# 10_LMS3_RF.net
KiCad netlist of a schematic drawn in Altium Designer
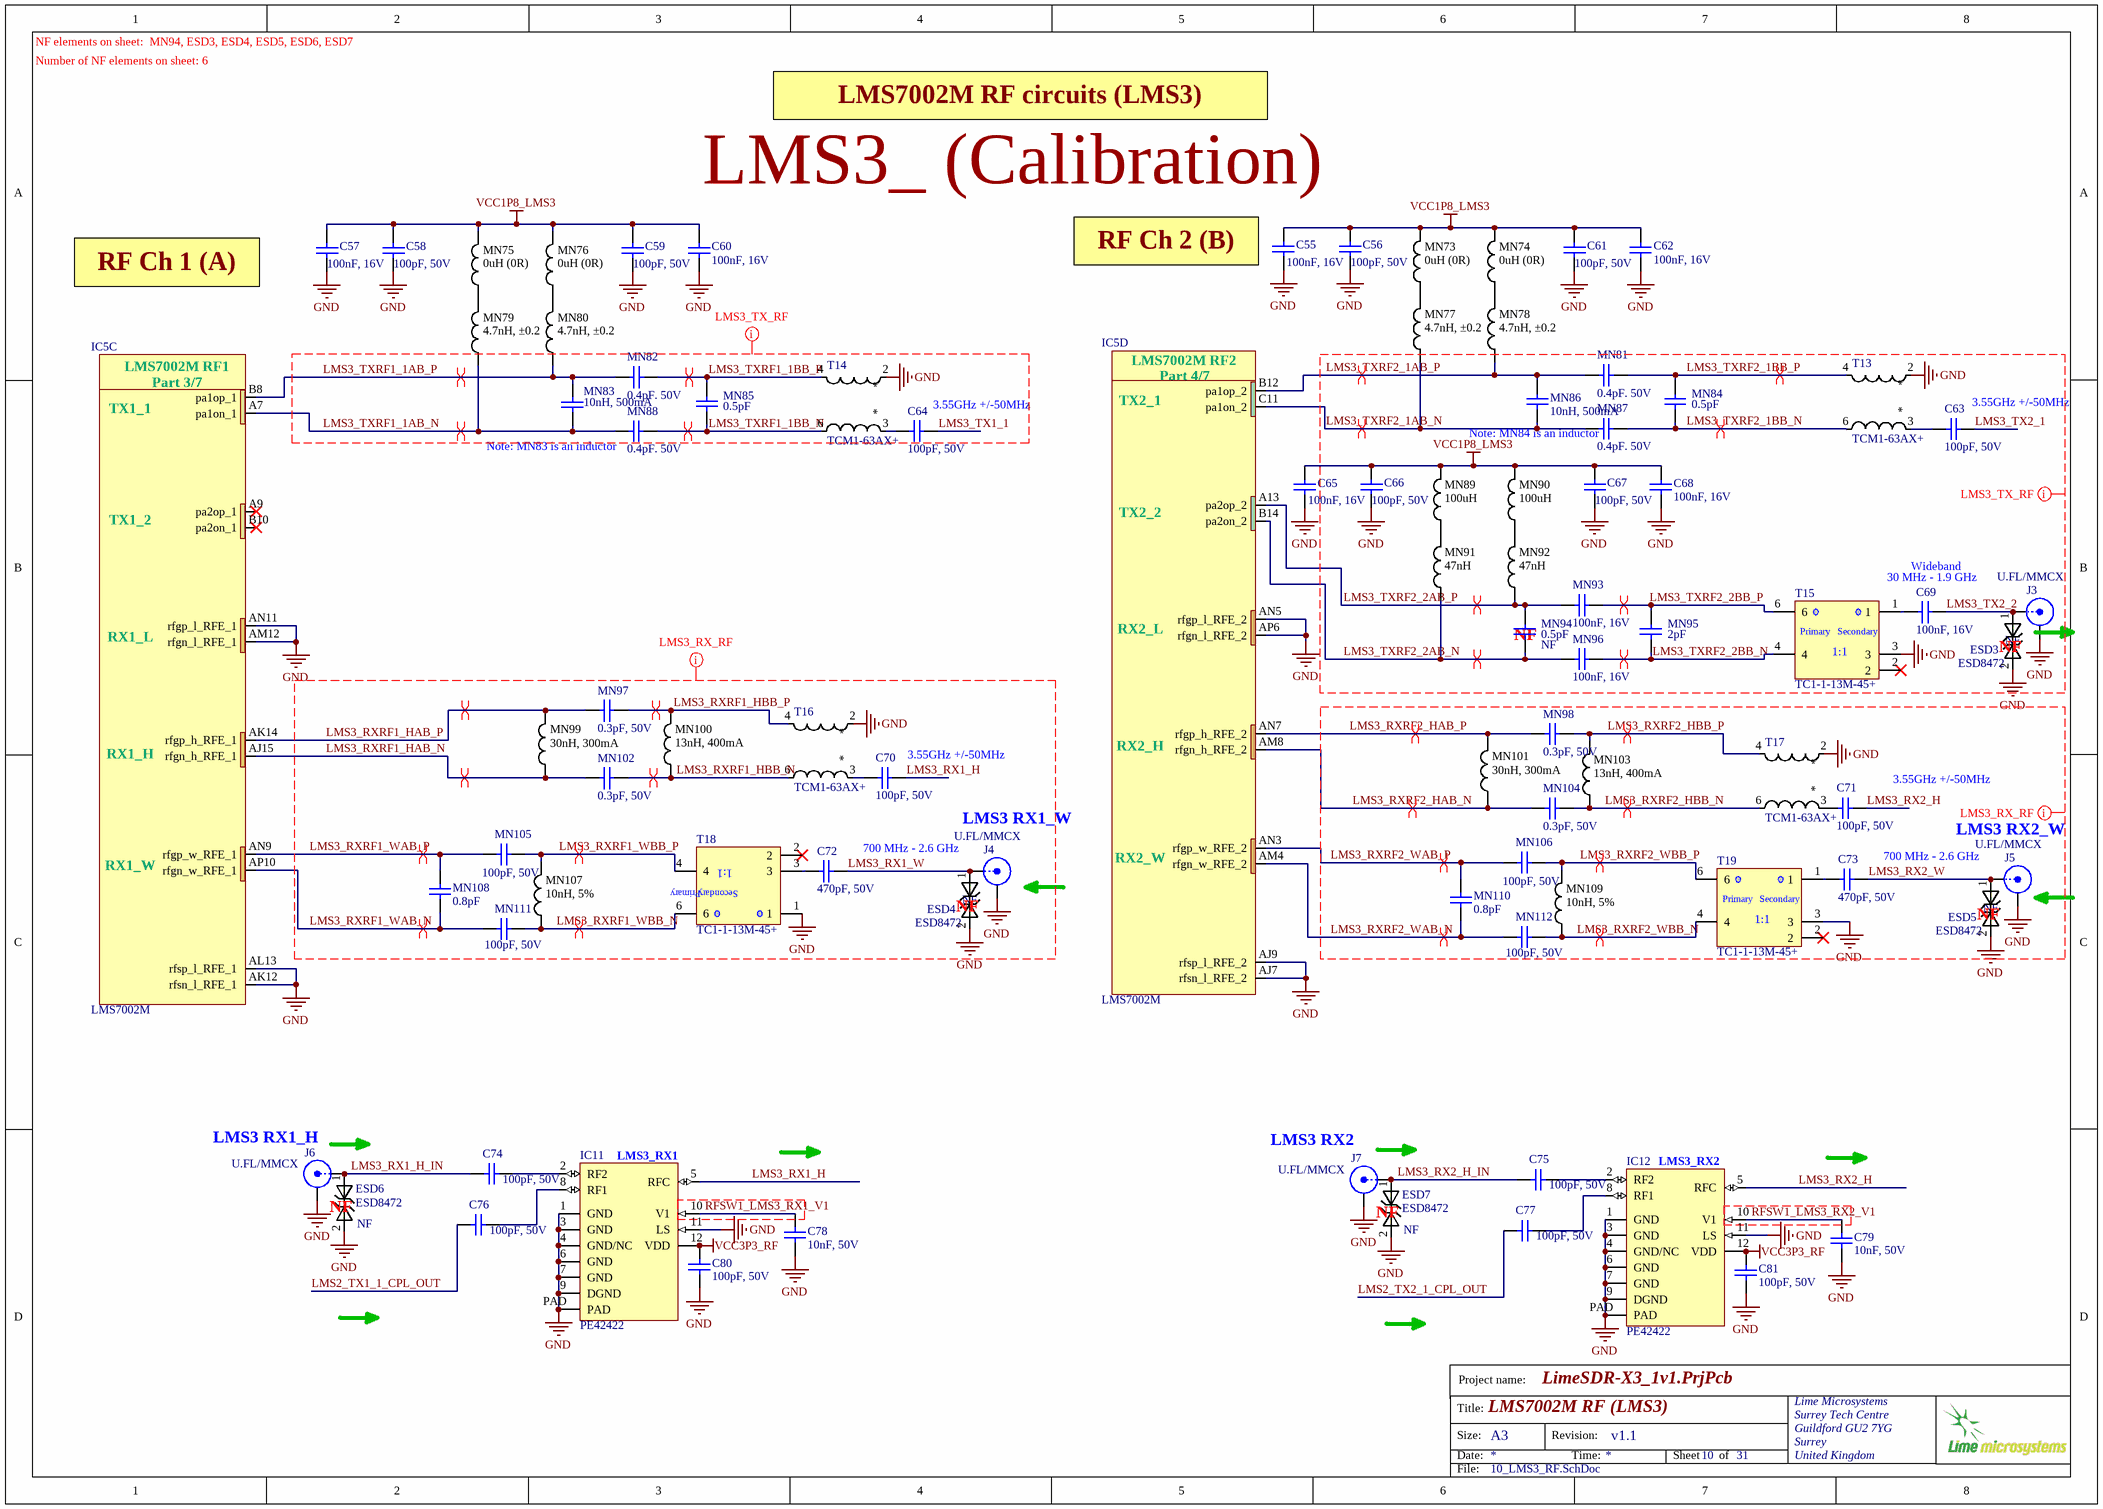
[diagram p0: 10_LMS3_RF.SchDoc]

(export (version "E")
  (design (tool "Eeschema 10.0.6"))
  (components
    (comp (ref "C55")
      (value "100nF, 16V")
      (footprint "CAP0402")
      (fields (field (name "MANUFACTURER") "Murata Electronics") (field (name "TOLERANCE") "10 %"))
      (libsource (lib "") (part "Cap_0402_2"))
    )
    (comp (ref "C56")
      (value "100pF, 50V")
      (footprint "CAP0402")
      (fields (field (name "MANUFACTURER") "Yageo") (field (name "TOLERANCE") "±5%"))
      (libsource (lib "") (part "Cap_0402_1"))
    )
    (comp (ref "C57")
      (value "100nF, 16V")
      (footprint "CAP0402")
      (fields (field (name "MANUFACTURER") "Murata Electronics") (field (name "TOLERANCE") "10 %"))
      (libsource (lib "LimeMicroAltiumLib_schLib") (part "Cap_0402"))
    )
    (comp (ref "C58")
      (value "100pF, 50V")
      (footprint "CAP0402")
      (fields (field (name "MANUFACTURER") "Yageo") (field (name "TOLERANCE") "±5%"))
      (libsource (lib "") (part "Cap_0402_1"))
    )
    (comp (ref "C59")
      (value "100pF, 50V")
      (footprint "CAP0402")
      (fields (field (name "MANUFACTURER") "Yageo") (field (name "TOLERANCE") "±5%"))
      (libsource (lib "") (part "Cap_0402_1"))
    )
    (comp (ref "C60")
      (value "100nF, 16V")
      (footprint "CAP0402")
      (fields (field (name "MANUFACTURER") "Murata Electronics") (field (name "TOLERANCE") "10 %"))
      (libsource (lib "LimeMicroAltiumLib_schLib") (part "Cap_0402"))
    )
    (comp (ref "C61")
      (value "100pF, 50V")
      (footprint "CAP0402")
      (fields (field (name "MANUFACTURER") "Yageo") (field (name "TOLERANCE") "±5%"))
      (libsource (lib "") (part "Cap_0402_1"))
    )
    (comp (ref "C62")
      (value "100nF, 16V")
      (footprint "CAP0402")
      (fields (field (name "MANUFACTURER") "Murata Electronics") (field (name "TOLERANCE") "10 %"))
      (libsource (lib "") (part "Cap_0402_2"))
    )
    (comp (ref "C63")
      (value "100pF, 50V")
      (footprint "CAP0402")
      (fields (field (name "TOLERANCE") "±5%") (field (name "MANUFACTURER") "Yageo"))
      (libsource (lib "") (part "Cap_0402_1"))
    )
    (comp (ref "C64")
      (value "100pF, 50V")
      (footprint "CAP0402")
      (fields (field (name "TOLERANCE") "±5%") (field (name "MANUFACTURER") "Yageo"))
      (libsource (lib "") (part "Cap_0402_1"))
    )
    (comp (ref "C65")
      (value "100nF, 16V")
      (footprint "CAP0402")
      (fields (field (name "MANUFACTURER") "Murata Electronics") (field (name "TOLERANCE") "10 %"))
      (libsource (lib "") (part "Cap_0402_3"))
    )
    (comp (ref "C66")
      (value "100pF, 50V")
      (footprint "CAP0402")
      (fields (field (name "MANUFACTURER") "Yageo") (field (name "TOLERANCE") "±5%"))
      (libsource (lib "") (part "Cap_0402_1"))
    )
    (comp (ref "C67")
      (value "100pF, 50V")
      (footprint "CAP0402")
      (fields (field (name "MANUFACTURER") "Yageo") (field (name "TOLERANCE") "±5%"))
      (libsource (lib "") (part "Cap_0402_1"))
    )
    (comp (ref "C68")
      (value "100nF, 16V")
      (footprint "CAP0402")
      (fields (field (name "MANUFACTURER") "Murata Electronics") (field (name "TOLERANCE") "10 %"))
      (libsource (lib "") (part "Cap_0402_3"))
    )
    (comp (ref "C69")
      (value "100nF, 16V")
      (footprint "CAP0402")
      (fields (field (name "MANUFACTURER") "Murata Electronics") (field (name "TOLERANCE") "10 %"))
      (libsource (lib "") (part "Cap_0402_11"))
    )
    (comp (ref "C70")
      (value "100pF, 50V")
      (footprint "CAP0402")
      (fields (field (name "TOLERANCE") "±5%") (field (name "MANUFACTURER") "Yageo"))
      (libsource (lib "") (part "Cap_0402_10"))
    )
    (comp (ref "C71")
      (value "100pF, 50V")
      (footprint "CAP0402")
      (fields (field (name "TOLERANCE") "±5%") (field (name "MANUFACTURER") "Yageo"))
      (libsource (lib "") (part "Cap_0402_10"))
    )
    (comp (ref "C72")
      (value "470pF, 50V")
      (footprint "CAP0402")
      (fields
        (field (name "MANUFACTURER PART NUMBER") "C1005C0G1H471J050BA")
        (field (name "TOLERANCE") "±5%")
        (field (name "MANUFACTURER") "TDK Corporation")
      )
      (libsource (lib "") (part "Cap_0402_9"))
    )
    (comp (ref "C73")
      (value "470pF, 50V")
      (footprint "CAP0402")
      (fields
        (field (name "MANUFACTURER PART NUMBER") "C1005C0G1H471J050BA")
        (field (name "TOLERANCE") "±5%")
        (field (name "MANUFACTURER") "TDK Corporation")
      )
      (libsource (lib "") (part "Cap_0402_9"))
    )
    (comp (ref "C74")
      (value "100pF, 50V")
      (footprint "CAP0402")
      (fields (field (name "TOLERANCE") "±5%") (field (name "MANUFACTURER") "Yageo"))
      (libsource (lib "") (part "Cap_0402_5"))
    )
    (comp (ref "C75")
      (value "100pF, 50V")
      (footprint "CAP0402")
      (fields (field (name "TOLERANCE") "±5%") (field (name "MANUFACTURER") "Yageo"))
      (libsource (lib "") (part "Cap_0402_5"))
    )
    (comp (ref "C76")
      (value "100pF, 50V")
      (footprint "CAP0402")
      (fields (field (name "TOLERANCE") "±5%") (field (name "MANUFACTURER") "Yageo"))
      (libsource (lib "") (part "Cap_0402_5"))
    )
    (comp (ref "C77")
      (value "100pF, 50V")
      (footprint "CAP0402")
      (fields (field (name "TOLERANCE") "±5%") (field (name "MANUFACTURER") "Yageo"))
      (libsource (lib "") (part "Cap_0402_5"))
    )
    (comp (ref "C78")
      (value "10nF, 50V")
      (footprint "CAP0402")
      (fields
        (field (name "MANUFACTURER") "Murata Electronics North America")
        (field (name "TOLERANCE") "±10%")
      )
      (libsource (lib "LimeMicroAltiumLib_schLib") (part "Cap_0402"))
    )
    (comp (ref "C79")
      (value "10nF, 50V")
      (footprint "CAP0402")
      (fields
        (field (name "MANUFACTURER") "Murata Electronics North America")
        (field (name "TOLERANCE") "±10%")
      )
      (libsource (lib "LimeMicroAltiumLib_schLib") (part "Cap_0402"))
    )
    (comp (ref "C80")
      (value "100pF, 50V")
      (footprint "CAP0402")
      (fields (field (name "TOLERANCE") "±5%") (field (name "MANUFACTURER") "Yageo"))
      (libsource (lib "") (part "Cap_0402_7"))
    )
    (comp (ref "C81")
      (value "100pF, 50V")
      (footprint "CAP0402")
      (fields (field (name "TOLERANCE") "±5%") (field (name "MANUFACTURER") "Yageo"))
      (libsource (lib "") (part "Cap_0402_7"))
    )
    (comp (ref "ESD3")
      (value "ESD8472")
      (footprint "ESD8472_X3DFN2")
      (fields (field (name "MANUFACTURER") "ON Semiconductor") (field (name "ASSEMBLY INFO") "NF"))
      (libsource (lib "LimeMicroAltiumLib_schLib") (part "ESD8472"))
    )
    (comp (ref "ESD4")
      (value "ESD8472")
      (footprint "ESD8472_X3DFN2")
      (fields (field (name "MANUFACTURER") "ON Semiconductor") (field (name "ASSEMBLY INFO") "NF"))
      (libsource (lib "LimeMicroAltiumLib_schLib") (part "ESD8472"))
    )
    (comp (ref "ESD5")
      (value "ESD8472")
      (footprint "ESD8472_X3DFN2")
      (fields (field (name "MANUFACTURER") "ON Semiconductor") (field (name "ASSEMBLY INFO") "NF"))
      (libsource (lib "LimeMicroAltiumLib_schLib") (part "ESD8472"))
    )
    (comp (ref "ESD6")
      (value "ESD8472")
      (footprint "ESD8472_X3DFN2")
      (fields (field (name "MANUFACTURER") "ON Semiconductor") (field (name "ASSEMBLY INFO") "NF"))
      (libsource (lib "LimeMicroAltiumLib_schLib") (part "ESD8472"))
    )
    (comp (ref "ESD7")
      (value "ESD8472")
      (footprint "ESD8472_X3DFN2")
      (fields (field (name "MANUFACTURER") "ON Semiconductor") (field (name "ASSEMBLY INFO") "NF"))
      (libsource (lib "LimeMicroAltiumLib_schLib") (part "ESD8472"))
    )
    (comp (ref "IC5")
      (value "LMS7002M")
      (footprint "LMS7002M_v5")
      (description "Schematic symbol revision 4. Default footprint - 0.31mm pad")
      (fields (field (name "MANUFACTURER") "Lime Microsystems"))
      (libsource (lib "LimeMicroAltiumLib_schLib_r04") (part "LMS7002Mr4"))
    )
    (comp (ref "IC11")
      (value "PE42422")
      (footprint "PE42422_QFN12")
      (fields (field (name "MANUFACTURER") "Peregrine Semiconductor"))
      (libsource (lib "LimeMicroAltiumLib_schLib") (part "PE42422"))
    )
    (comp (ref "IC12")
      (value "PE42422")
      (footprint "PE42422_QFN12")
      (fields (field (name "MANUFACTURER") "Peregrine Semiconductor"))
      (libsource (lib "LimeMicroAltiumLib_schLib") (part "PE42422"))
    )
    (comp (ref "J3")
      (value "U.FL/MMCX")
      (footprint "MMCX_UFL_conn_m")
      (description "CONN UMC RCPT STR 50 OHM SMD")
      (fields (field (name "MANUFACTURER") "Amphenol RF"))
      (libsource (lib "LimeMicroAltiumLib_schLib") (part "RF_IF_connector"))
    )
    (comp (ref "J4")
      (value "U.FL/MMCX")
      (footprint "MMCX_UFL_conn_m")
      (description "CONN UMC RCPT STR 50 OHM SMD")
      (fields (field (name "MANUFACTURER") "Amphenol RF"))
      (libsource (lib "LimeMicroAltiumLib_schLib") (part "RF_IF_connector"))
    )
    (comp (ref "J5")
      (value "U.FL/MMCX")
      (footprint "MMCX_UFL_conn_m")
      (description "CONN UMC RCPT STR 50 OHM SMD")
      (fields (field (name "MANUFACTURER") "Amphenol RF"))
      (libsource (lib "LimeMicroAltiumLib_schLib") (part "RF_IF_connector"))
    )
    (comp (ref "J6")
      (value "U.FL/MMCX")
      (footprint "MMCX_UFL_conn_m")
      (description "CONN UMC RCPT STR 50 OHM SMD")
      (fields (field (name "MANUFACTURER") "Amphenol RF"))
      (libsource (lib "LimeMicroAltiumLib_schLib") (part "RF_IF_connector"))
    )
    (comp (ref "J7")
      (value "U.FL/MMCX")
      (footprint "MMCX_UFL_conn_m")
      (description "CONN UMC RCPT STR 50 OHM SMD")
      (fields (field (name "MANUFACTURER") "Amphenol RF"))
      (libsource (lib "LimeMicroAltiumLib_schLib") (part "RF_IF_connector"))
    )
    (comp (ref "MN73")
      (value "0uH (0R)")
      (footprint "RES0603")
      (fields
        (field (name "MANUFACTURER") "Panasonic Electronic Components")
        (field (name "MANUFACTURER PART NUMBER") "ERJ-3GEY0R00V")
        (field (name "TOLERANCE") "Jumper")
      )
      (libsource (lib "") (part "Inductor_0603_1"))
    )
    (comp (ref "MN74")
      (value "0uH (0R)")
      (footprint "RES0603")
      (fields
        (field (name "MANUFACTURER") "Panasonic Electronic Components")
        (field (name "MANUFACTURER PART NUMBER") "ERJ-3GEY0R00V")
        (field (name "TOLERANCE") "Jumper")
      )
      (libsource (lib "") (part "Inductor_0603_1"))
    )
    (comp (ref "MN75")
      (value "0uH (0R)")
      (footprint "RES0603")
      (fields
        (field (name "MANUFACTURER") "Panasonic Electronic Components")
        (field (name "MANUFACTURER PART NUMBER") "ERJ-3GEY0R00V")
        (field (name "TOLERANCE") "Jumper")
      )
      (libsource (lib "") (part "Inductor_0603_1"))
    )
    (comp (ref "MN76")
      (value "0uH (0R)")
      (footprint "RES0603")
      (fields
        (field (name "MANUFACTURER") "Panasonic Electronic Components")
        (field (name "MANUFACTURER PART NUMBER") "ERJ-3GEY0R00V")
        (field (name "TOLERANCE") "Jumper")
      )
      (libsource (lib "") (part "Inductor_0603_1"))
    )
    (comp (ref "MN77")
      (value "4.7nH, ±0.2")
      (footprint "RES0402")
      (fields (field (name "MANUFACTURER") "Murata"))
      (libsource (lib "") (part "Inductor_0603_2"))
    )
    (comp (ref "MN78")
      (value "4.7nH, ±0.2")
      (footprint "RES0402")
      (fields (field (name "MANUFACTURER") "Murata"))
      (libsource (lib "") (part "Inductor_0603_2"))
    )
    (comp (ref "MN79")
      (value "4.7nH, ±0.2")
      (footprint "RES0402")
      (fields (field (name "MANUFACTURER") "Murata"))
      (libsource (lib "") (part "Inductor_0603_2"))
    )
    (comp (ref "MN80")
      (value "4.7nH, ±0.2")
      (footprint "RES0402")
      (fields (field (name "MANUFACTURER") "Murata"))
      (libsource (lib "") (part "Inductor_0603_2"))
    )
    (comp (ref "MN81")
      (value "0.4pF. 50V")
      (footprint "CAP0402")
      (fields (field (name "MANUFACTURER") "Murata"))
      (libsource (lib "") (part "Cap_0402_3"))
    )
    (comp (ref "MN82")
      (value "0.4pF. 50V")
      (footprint "CAP0402")
      (fields (field (name "MANUFACTURER") "Murata"))
      (libsource (lib "") (part "Cap_0402_3"))
    )
    (comp (ref "MN83")
      (value "10nH, 500mA")
      (footprint "CAP0402")
      (fields (field (name "MANUFACTURER") "Murata") (field (name "TOLERANCE") "2%"))
      (libsource (lib "LimeMicroAltiumLib_schLib") (part "Cap_0402"))
    )
    (comp (ref "MN84")
      (value "0.5pF")
      (footprint "CAP0402")
      (fields (field (name "TOLERANCE") "±0.25pF") (field (name "MANUFACTURER") "Yageo"))
      (libsource (lib "") (part "Cap_0402_6"))
    )
    (comp (ref "MN85")
      (value "0.5pF")
      (footprint "CAP0402")
      (fields (field (name "TOLERANCE") "±0.25pF") (field (name "MANUFACTURER") "Yageo"))
      (libsource (lib "") (part "Cap_0402_6"))
    )
    (comp (ref "MN86")
      (value "10nH, 500mA")
      (footprint "CAP0402")
      (fields (field (name "MANUFACTURER") "Murata") (field (name "TOLERANCE") "2%"))
      (libsource (lib "LimeMicroAltiumLib_schLib") (part "Cap_0402"))
    )
    (comp (ref "MN87")
      (value "0.4pF. 50V")
      (footprint "CAP0402")
      (fields (field (name "MANUFACTURER") "Murata"))
      (libsource (lib "") (part "Cap_0402_4"))
    )
    (comp (ref "MN88")
      (value "0.4pF. 50V")
      (footprint "CAP0402")
      (fields (field (name "MANUFACTURER") "Murata"))
      (libsource (lib "") (part "Cap_0402_4"))
    )
    (comp (ref "MN89")
      (value "100uH")
      (footprint "RES0603")
      (fields
        (field (name "MANUFACTURER") "TDK Corporation")
        (field (name "MANUFACTURER PART NUMBER") "GLFR1608T101M-LR")
        (field (name "TOLERANCE") "±20%")
      )
      (libsource (lib "LimeMicroAltiumLib_schLib") (part "Inductor_0603"))
    )
    (comp (ref "MN90")
      (value "100uH")
      (footprint "RES0603")
      (fields
        (field (name "MANUFACTURER") "TDK Corporation")
        (field (name "MANUFACTURER PART NUMBER") "GLFR1608T101M-LR")
        (field (name "TOLERANCE") "±20%")
      )
      (libsource (lib "LimeMicroAltiumLib_schLib") (part "Inductor_0603"))
    )
    (comp (ref "MN91")
      (value "47nH")
      (footprint "RES0402")
      (fields (field (name "MANUFACTURER") "COILCRAFT"))
      (libsource (lib "LimeMicroAltiumLib_schLib") (part "Inductor_0603"))
    )
    (comp (ref "MN92")
      (value "47nH")
      (footprint "RES0402")
      (fields (field (name "MANUFACTURER") "COILCRAFT"))
      (libsource (lib "LimeMicroAltiumLib_schLib") (part "Inductor_0603"))
    )
    (comp (ref "MN93")
      (value "100nF, 16V")
      (footprint "CAP0402")
      (fields (field (name "MANUFACTURER") "Murata Electronics") (field (name "TOLERANCE") "10 %"))
      (libsource (lib "") (part "Cap_0402_2"))
    )
    (comp (ref "MN94")
      (value "0.5pF")
      (footprint "CAP0402")
      (fields
        (field (name "ASSEMBLY INFO") "NF")
        (field (name "TOLERANCE") "±0.25pF")
        (field (name "MANUFACTURER") "Yageo")
      )
      (libsource (lib "") (part "Cap_0402_3"))
    )
    (comp (ref "MN95")
      (value "2pF")
      (footprint "CAP0402")
      (fields (field (name "MANUFACTURER PART NUMBER") "04025U2R0BAT2A") (field (name "MANUFACTURER") "AVX"))
      (libsource (lib "") (part "Cap_0402_3"))
    )
    (comp (ref "MN96")
      (value "100nF, 16V")
      (footprint "CAP0402")
      (fields (field (name "MANUFACTURER") "Murata Electronics") (field (name "TOLERANCE") "10 %"))
      (libsource (lib "") (part "Cap_0402_12"))
    )
    (comp (ref "MN97")
      (value "0.3pF, 50V")
      (footprint "CAP0402")
      (fields (field (name "MANUFACTURER") "Johanson"))
      (libsource (lib "") (part "Cap_0402_8"))
    )
    (comp (ref "MN98")
      (value "0.3pF, 50V")
      (footprint "CAP0402")
      (fields (field (name "MANUFACTURER") "Johanson"))
      (libsource (lib "") (part "Cap_0402_8"))
    )
    (comp (ref "MN99")
      (value "30nH, 300mA")
      (footprint "RES0402")
      (fields (field (name "MANUFACTURER") "TDK") (field (name "TOLERANCE") "5%"))
      (libsource (lib "LimeMicroAltiumLib_schLib") (part "Inductor_0603"))
    )
    (comp (ref "MN100")
      (value "13nH, 400mA")
      (footprint "RES0402")
      (fields (field (name "MANUFACTURER") "TDK") (field (name "TOLERANCE") "5%"))
      (libsource (lib "") (part "Inductor_0603_2"))
    )
    (comp (ref "MN101")
      (value "30nH, 300mA")
      (footprint "RES0402")
      (fields (field (name "MANUFACTURER") "TDK") (field (name "TOLERANCE") "5%"))
      (libsource (lib "LimeMicroAltiumLib_schLib") (part "Inductor_0603"))
    )
    (comp (ref "MN102")
      (value "0.3pF, 50V")
      (footprint "CAP0402")
      (fields (field (name "MANUFACTURER") "Johanson"))
      (libsource (lib "") (part "Cap_0402_8"))
    )
    (comp (ref "MN103")
      (value "13nH, 400mA")
      (footprint "RES0402")
      (fields (field (name "MANUFACTURER") "TDK") (field (name "TOLERANCE") "5%"))
      (libsource (lib "") (part "Inductor_0603_2"))
    )
    (comp (ref "MN104")
      (value "0.3pF, 50V")
      (footprint "CAP0402")
      (fields (field (name "MANUFACTURER") "Johanson"))
      (libsource (lib "") (part "Cap_0402_8"))
    )
    (comp (ref "MN105")
      (value "100pF, 50V")
      (footprint "CAP0402")
      (fields (field (name "TOLERANCE") "±5%") (field (name "MANUFACTURER") "Yageo"))
      (libsource (lib "") (part "Cap_0402_9"))
    )
    (comp (ref "MN106")
      (value "100pF, 50V")
      (footprint "CAP0402")
      (fields (field (name "TOLERANCE") "±5%") (field (name "MANUFACTURER") "Yageo"))
      (libsource (lib "") (part "Cap_0402_9"))
    )
    (comp (ref "MN107")
      (value "10nH, 5%")
      (footprint "RES0402")
      (fields (field (name "MANUFACTURER") "COILCRAFT"))
      (libsource (lib "") (part "Inductor_0603_3"))
    )
    (comp (ref "MN108")
      (value "0.8pF")
      (footprint "CAP0402")
      (fields
        (field (name "TOLERANCE") "±0.1pF")
        (field (name "MANUFACTURER") "Murata Electronics North America")
        (field (name "MANUFACTURER PART NUMBER") "GRM1555C1HR80BA01D")
      )
      (libsource (lib "") (part "Cap_0402_9"))
    )
    (comp (ref "MN109")
      (value "10nH, 5%")
      (footprint "RES0402")
      (fields (field (name "MANUFACTURER") "COILCRAFT"))
      (libsource (lib "") (part "Inductor_0603_3"))
    )
    (comp (ref "MN110")
      (value "0.8pF")
      (footprint "CAP0402")
      (fields
        (field (name "TOLERANCE") "±0.1pF")
        (field (name "MANUFACTURER") "Murata Electronics North America")
        (field (name "MANUFACTURER PART NUMBER") "GRM1555C1HR80BA01D")
      )
      (libsource (lib "") (part "Cap_0402_9"))
    )
    (comp (ref "MN111")
      (value "100pF, 50V")
      (footprint "CAP0402")
      (fields (field (name "TOLERANCE") "±5%") (field (name "MANUFACTURER") "Yageo"))
      (libsource (lib "") (part "Cap_0402_9"))
    )
    (comp (ref "MN112")
      (value "100pF, 50V")
      (footprint "CAP0402")
      (fields (field (name "TOLERANCE") "±5%") (field (name "MANUFACTURER") "Yageo"))
      (libsource (lib "") (part "Cap_0402_9"))
    )
    (comp (ref "T13")
      (value "TCM1-63AX+")
      (footprint "TCM1-63AX+_v2")
      (fields (field (name "MANUFACTURER") "Mini-circuits"))
      (libsource (lib "LimeMicroAltiumLib_schLib") (part "Balun_v2"))
    )
    (comp (ref "T14")
      (value "TCM1-63AX+")
      (footprint "TCM1-63AX+_v2")
      (fields (field (name "MANUFACTURER") "Mini-circuits"))
      (libsource (lib "LimeMicroAltiumLib_schLib") (part "Balun_v2"))
    )
    (comp (ref "T15")
      (value "TC1-1-13M-45+")
      (footprint "TC1-1-13MA+_JA4220-AL_")
      (fields (field (name "MANUFACTURER") "Minicircuits"))
      (libsource (lib "") (part "TC1-1-13M+_1"))
    )
    (comp (ref "T16")
      (value "TCM1-63AX+")
      (footprint "TCM1-63AX+_v2")
      (fields (field (name "MANUFACTURER") "Mini-circuits"))
      (libsource (lib "") (part "Balun_v2_1"))
    )
    (comp (ref "T17")
      (value "TCM1-63AX+")
      (footprint "TCM1-63AX+_v2")
      (fields (field (name "MANUFACTURER") "Mini-circuits"))
      (libsource (lib "") (part "Balun_v2_1"))
    )
    (comp (ref "T18")
      (value "TC1-1-13M-45+")
      (footprint "TC1-1-13MA+_JA4220-AL_")
      (fields (field (name "MANUFACTURER") "Minicircuits"))
      (libsource (lib "LimeMicroAltiumLib_schLib") (part "TC1-1-13M+"))
    )
    (comp (ref "T19")
      (value "TC1-1-13M-45+")
      (footprint "TC1-1-13MA+_JA4220-AL_")
      (fields (field (name "MANUFACTURER") "Minicircuits"))
      (libsource (lib "") (part "TC1-1-13M+_1"))
    )
  )
  (nets
    (net (code "1") (name "/LMS2_TX1_1_CPL_OUT") (class "Default")
      (node (ref "C76") (pin "2") (pinfunction "2_2") (pintype "passive"))
    )
    (net (code "2") (name "/LMS2_TX2_1_CPL_OUT") (class "Default")
      (node (ref "C77") (pin "2") (pinfunction "2_2") (pintype "passive"))
    )
    (net (code "3") (name "/LMS3_RX1_H") (class "Default")
      (node (ref "C70") (pin "1") (pinfunction "1_1") (pintype "passive"))
      (node (ref "IC11") (pin "5") (pinfunction "RFC_5") (pintype "bidirectional"))
    )
    (net (code "4") (name "/LMS3_RX1_H_IN") (class "Default")
      (node (ref "C74") (pin "2") (pinfunction "2_2") (pintype "passive"))
      (node (ref "ESD6") (pin "1") (pinfunction "1_1") (pintype "passive"))
      (node (ref "J6") (pin "1") (pinfunction "X_1") (pintype "passive"))
    )
    (net (code "5") (name "/LMS3_RX1_W") (class "Default")
      (node (ref "C72") (pin "1") (pinfunction "1_1") (pintype "passive"))
      (node (ref "ESD4") (pin "1") (pinfunction "1_1") (pintype "passive"))
      (node (ref "J4") (pin "1") (pinfunction "X_1") (pintype "passive"))
    )
    (net (code "6") (name "/LMS3_RX2_H") (class "Default")
      (node (ref "C71") (pin "1") (pinfunction "1_1") (pintype "passive"))
      (node (ref "IC12") (pin "5") (pinfunction "RFC_5") (pintype "bidirectional"))
    )
    (net (code "7") (name "/LMS3_RX2_H_IN") (class "Default")
      (node (ref "C75") (pin "2") (pinfunction "2_2") (pintype "passive"))
      (node (ref "ESD7") (pin "1") (pinfunction "1_1") (pintype "passive"))
      (node (ref "J7") (pin "1") (pinfunction "X_1") (pintype "passive"))
    )
    (net (code "8") (name "/LMS3_RX2_W") (class "Default")
      (node (ref "C73") (pin "1") (pinfunction "1_1") (pintype "passive"))
      (node (ref "ESD5") (pin "1") (pinfunction "1_1") (pintype "passive"))
      (node (ref "J5") (pin "1") (pinfunction "X_1") (pintype "passive"))
    )
    (net (code "9") (name "/LMS3_RXRF1_HAB_N") (class "Default")
      (node (ref "IC5") (pin "AJ15") (pinfunction "rfgn_h_RFE_1_AJ15") (pintype "passive"))
      (node (ref "MN102") (pin "2") (pinfunction "2_2") (pintype "passive"))
      (node (ref "MN99") (pin "1") (pinfunction "1_1") (pintype "passive"))
    )
    (net (code "10") (name "/LMS3_RXRF1_HAB_P") (class "Default")
      (node (ref "IC5") (pin "AK14") (pinfunction "rfgp_h_RFE_1_AK14") (pintype "passive"))
      (node (ref "MN97") (pin "2") (pinfunction "2_2") (pintype "passive"))
      (node (ref "MN99") (pin "2") (pinfunction "2_2") (pintype "passive"))
    )
    (net (code "11") (name "/LMS3_RXRF1_HBB_N") (class "Default")
      (node (ref "MN100") (pin "1") (pinfunction "1_1") (pintype "passive"))
      (node (ref "MN102") (pin "1") (pinfunction "1_1") (pintype "passive"))
      (node (ref "T16") (pin "6") (pinfunction "6_6") (pintype "passive"))
    )
    (net (code "12") (name "/LMS3_RXRF1_HBB_P") (class "Default")
      (node (ref "MN100") (pin "2") (pinfunction "2_2") (pintype "passive"))
      (node (ref "MN97") (pin "1") (pinfunction "1_1") (pintype "passive"))
      (node (ref "T16") (pin "4") (pinfunction "4_4") (pintype "passive"))
    )
    (net (code "13") (name "/LMS3_RXRF1_WAB_N") (class "Default")
      (node (ref "IC5") (pin "AP10") (pinfunction "rfgn_w_RFE_1_AP10") (pintype "passive"))
      (node (ref "MN108") (pin "2") (pinfunction "2_2") (pintype "passive"))
      (node (ref "MN111") (pin "2") (pinfunction "2_2") (pintype "passive"))
    )
    (net (code "14") (name "/LMS3_RXRF1_WAB_P") (class "Default")
      (node (ref "IC5") (pin "AN9") (pinfunction "rfgp_w_RFE_1_AN9") (pintype "passive"))
      (node (ref "MN105") (pin "2") (pinfunction "2_2") (pintype "passive"))
      (node (ref "MN108") (pin "1") (pinfunction "1_1") (pintype "passive"))
    )
    (net (code "15") (name "/LMS3_RXRF1_WBB_N") (class "Default")
      (node (ref "MN107") (pin "1") (pinfunction "1_1") (pintype "passive"))
      (node (ref "MN111") (pin "1") (pinfunction "1_1") (pintype "passive"))
      (node (ref "T18") (pin "6") (pinfunction "6_6") (pintype "passive"))
    )
    (net (code "16") (name "/LMS3_RXRF1_WBB_P") (class "Default")
      (node (ref "MN105") (pin "1") (pinfunction "1_1") (pintype "passive"))
      (node (ref "MN107") (pin "2") (pinfunction "2_2") (pintype "passive"))
      (node (ref "T18") (pin "4") (pinfunction "4_4") (pintype "passive"))
    )
    (net (code "18") (name "/LMS3_RXRF2_HAB_P") (class "Default")
      (node (ref "IC5") (pin "AN7") (pinfunction "rfgp_h_RFE_2_AN7") (pintype "passive"))
      (node (ref "MN101") (pin "2") (pinfunction "2_2") (pintype "passive"))
      (node (ref "MN98") (pin "2") (pinfunction "2_2") (pintype "passive"))
    )
    (net (code "19") (name "/LMS3_RXRF2_HBB_N") (class "Default")
      (node (ref "MN103") (pin "1") (pinfunction "1_1") (pintype "passive"))
      (node (ref "MN104") (pin "1") (pinfunction "1_1") (pintype "passive"))
      (node (ref "T17") (pin "6") (pinfunction "6_6") (pintype "passive"))
    )
    (net (code "20") (name "/LMS3_RXRF2_HBB_P") (class "Default")
      (node (ref "MN103") (pin "2") (pinfunction "2_2") (pintype "passive"))
      (node (ref "MN98") (pin "1") (pinfunction "1_1") (pintype "passive"))
      (node (ref "T17") (pin "4") (pinfunction "4_4") (pintype "passive"))
    )
    (net (code "21") (name "/LMS3_RXRF2_WAB_N") (class "Default")
      (node (ref "IC5") (pin "AM4") (pinfunction "rfgn_w_RFE_2_AM4") (pintype "passive"))
      (node (ref "MN110") (pin "2") (pinfunction "2_2") (pintype "passive"))
      (node (ref "MN112") (pin "2") (pinfunction "2_2") (pintype "passive"))
    )
    (net (code "22") (name "/LMS3_RXRF2_WAB_P") (class "Default")
      (node (ref "IC5") (pin "AN3") (pinfunction "rfgp_w_RFE_2_AN3") (pintype "passive"))
      (node (ref "MN106") (pin "2") (pinfunction "2_2") (pintype "passive"))
      (node (ref "MN110") (pin "1") (pinfunction "1_1") (pintype "passive"))
    )
    (net (code "23") (name "/LMS3_RXRF2_WBB_N") (class "Default")
      (node (ref "MN109") (pin "1") (pinfunction "1_1") (pintype "passive"))
      (node (ref "MN112") (pin "1") (pinfunction "1_1") (pintype "passive"))
      (node (ref "T19") (pin "4") (pinfunction "4_4") (pintype "passive"))
    )
    (net (code "24") (name "/LMS3_RXRF2_WBB_P") (class "Default")
      (node (ref "MN106") (pin "1") (pinfunction "1_1") (pintype "passive"))
      (node (ref "MN109") (pin "2") (pinfunction "2_2") (pintype "passive"))
      (node (ref "T19") (pin "6") (pinfunction "6_6") (pintype "passive"))
    )
    (net (code "25") (name "/LMS3_TX1_1") (class "Default")
      (node (ref "C64") (pin "1") (pinfunction "1_1") (pintype "passive"))
    )
    (net (code "26") (name "/LMS3_TX2_1") (class "Default")
      (node (ref "C63") (pin "1") (pinfunction "1_1") (pintype "passive"))
    )
    (net (code "27") (name "/LMS3_TX2_2") (class "Default")
      (node (ref "C69") (pin "1") (pinfunction "1_1") (pintype "passive"))
      (node (ref "ESD3") (pin "1") (pinfunction "1_1") (pintype "passive"))
      (node (ref "J3") (pin "1") (pinfunction "X_1") (pintype "passive"))
    )
    (net (code "28") (name "/LMS3_TXRF1_1AB_N") (class "Default")
      (node (ref "IC5") (pin "A7") (pinfunction "pa1on_1_A7") (pintype "passive"))
      (node (ref "MN79") (pin "1") (pinfunction "1_1") (pintype "passive"))
      (node (ref "MN83") (pin "2") (pinfunction "2_2") (pintype "passive"))
      (node (ref "MN88") (pin "2") (pinfunction "2_2") (pintype "passive"))
    )
    (net (code "29") (name "/LMS3_TXRF1_1AB_P") (class "Default")
      (node (ref "IC5") (pin "B8") (pinfunction "pa1op_1_B8") (pintype "passive"))
      (node (ref "MN80") (pin "1") (pinfunction "1_1") (pintype "passive"))
      (node (ref "MN82") (pin "2") (pinfunction "2_2") (pintype "passive"))
      (node (ref "MN83") (pin "1") (pinfunction "1_1") (pintype "passive"))
    )
    (net (code "30") (name "/LMS3_TXRF1_1BB_N") (class "Default")
      (node (ref "MN85") (pin "1") (pinfunction "1_1") (pintype "passive"))
      (node (ref "MN88") (pin "1") (pinfunction "1_1") (pintype "passive"))
      (node (ref "T14") (pin "6") (pinfunction "6_6") (pintype "passive"))
    )
    (net (code "31") (name "/LMS3_TXRF1_1BB_P") (class "Default")
      (node (ref "MN82") (pin "1") (pinfunction "1_1") (pintype "passive"))
      (node (ref "MN85") (pin "2") (pinfunction "2_2") (pintype "passive"))
      (node (ref "T14") (pin "4") (pinfunction "4_4") (pintype "passive"))
    )
    (net (code "32") (name "/LMS3_TXRF2_1AB_N") (class "Default")
      (node (ref "IC5") (pin "C11") (pinfunction "pa1on_2_C11") (pintype "passive"))
      (node (ref "MN77") (pin "1") (pinfunction "1_1") (pintype "passive"))
      (node (ref "MN86") (pin "1") (pinfunction "1_1") (pintype "passive"))
      (node (ref "MN87") (pin "2") (pinfunction "2_2") (pintype "passive"))
    )
    (net (code "33") (name "/LMS3_TXRF2_1AB_P") (class "Default")
      (node (ref "IC5") (pin "B12") (pinfunction "pa1op_2_B12") (pintype "passive"))
      (node (ref "MN78") (pin "1") (pinfunction "1_1") (pintype "passive"))
      (node (ref "MN81") (pin "2") (pinfunction "2_2") (pintype "passive"))
      (node (ref "MN86") (pin "2") (pinfunction "2_2") (pintype "passive"))
    )
    (net (code "34") (name "/LMS3_TXRF2_1BB_N") (class "Default")
      (node (ref "MN84") (pin "1") (pinfunction "1_1") (pintype "passive"))
      (node (ref "MN87") (pin "1") (pinfunction "1_1") (pintype "passive"))
      (node (ref "T13") (pin "6") (pinfunction "6_6") (pintype "passive"))
    )
    (net (code "35") (name "/LMS3_TXRF2_1BB_P") (class "Default")
      (node (ref "MN81") (pin "1") (pinfunction "1_1") (pintype "passive"))
      (node (ref "MN84") (pin "2") (pinfunction "2_2") (pintype "passive"))
      (node (ref "T13") (pin "4") (pinfunction "4_4") (pintype "passive"))
    )
    (net (code "36") (name "/LMS3_TXRF2_2AB_N") (class "Default")
      (node (ref "IC5") (pin "B14") (pinfunction "pa2on_2_B14") (pintype "passive"))
      (node (ref "MN91") (pin "1") (pinfunction "1_1") (pintype "passive"))
      (node (ref "MN94") (pin "1") (pinfunction "1_1") (pintype "passive"))
      (node (ref "MN96") (pin "1") (pinfunction "1_1") (pintype "passive"))
    )
    (net (code "37") (name "/LMS3_TXRF2_2AB_P") (class "Default")
      (node (ref "IC5") (pin "A13") (pinfunction "pa2op_2_A13") (pintype "passive"))
      (node (ref "MN92") (pin "1") (pinfunction "1_1") (pintype "passive"))
      (node (ref "MN93") (pin "2") (pinfunction "2_2") (pintype "passive"))
      (node (ref "MN94") (pin "2") (pinfunction "2_2") (pintype "passive"))
    )
    (net (code "38") (name "/LMS3_TXRF2_2BB_N") (class "Default")
      (node (ref "MN95") (pin "1") (pinfunction "1_1") (pintype "passive"))
      (node (ref "MN96") (pin "2") (pinfunction "2_2") (pintype "passive"))
      (node (ref "T15") (pin "4") (pinfunction "4_4") (pintype "passive"))
    )
    (net (code "39") (name "/LMS3_TXRF2_2BB_P") (class "Default")
      (node (ref "MN93") (pin "1") (pinfunction "1_1") (pintype "passive"))
      (node (ref "MN95") (pin "2") (pinfunction "2_2") (pintype "passive"))
      (node (ref "T15") (pin "6") (pinfunction "6_6") (pintype "passive"))
    )
    (net (code "40") (name "/RFSW1_LMS3_RX1_V1") (class "Default")
      (node (ref "C78") (pin "1") (pinfunction "1_1") (pintype "passive"))
      (node (ref "IC11") (pin "10") (pinfunction "V1_10") (pintype "input"))
    )
    (net (code "41") (name "/RFSW1_LMS3_RX2_V1") (class "Default")
      (node (ref "C79") (pin "1") (pinfunction "1_1") (pintype "passive"))
      (node (ref "IC12") (pin "10") (pinfunction "V1_10") (pintype "input"))
    )
    (net (code "42") (name "GND") (class "Default")
      (node (ref "C55") (pin "1") (pinfunction "1_1") (pintype "passive"))
      (node (ref "C56") (pin "1") (pinfunction "1_1") (pintype "passive"))
      (node (ref "C57") (pin "1") (pinfunction "1_1") (pintype "passive"))
      (node (ref "C58") (pin "1") (pinfunction "1_1") (pintype "passive"))
      (node (ref "C59") (pin "1") (pinfunction "1_1") (pintype "passive"))
      (node (ref "C60") (pin "1") (pinfunction "1_1") (pintype "passive"))
      (node (ref "C61") (pin "1") (pinfunction "1_1") (pintype "passive"))
      (node (ref "C62") (pin "1") (pinfunction "1_1") (pintype "passive"))
      (node (ref "C65") (pin "1") (pinfunction "1_1") (pintype "passive"))
      (node (ref "C66") (pin "1") (pinfunction "1_1") (pintype "passive"))
      (node (ref "C67") (pin "1") (pinfunction "1_1") (pintype "passive"))
      (node (ref "C68") (pin "1") (pinfunction "1_1") (pintype "passive"))
      (node (ref "C78") (pin "2") (pinfunction "2_2") (pintype "passive"))
      (node (ref "C79") (pin "2") (pinfunction "2_2") (pintype "passive"))
      (node (ref "C80") (pin "1") (pinfunction "1_1") (pintype "passive"))
      (node (ref "C81") (pin "1") (pinfunction "1_1") (pintype "passive"))
      (node (ref "ESD3") (pin "2") (pinfunction "2_2") (pintype "passive"))
      (node (ref "ESD4") (pin "2") (pinfunction "2_2") (pintype "passive"))
      (node (ref "ESD5") (pin "2") (pinfunction "2_2") (pintype "passive"))
      (node (ref "ESD6") (pin "2") (pinfunction "2_2") (pintype "passive"))
      (node (ref "ESD7") (pin "2") (pinfunction "2_2") (pintype "passive"))
      (node (ref "IC11") (pin "1") (pinfunction "GND_1") (pintype "passive"))
      (node (ref "IC11") (pin "11") (pinfunction "LS_11") (pintype "input"))
      (node (ref "IC11") (pin "3") (pinfunction "GND_3") (pintype "passive"))
      (node (ref "IC11") (pin "4") (pinfunction "GND/NC_4") (pintype "passive"))
      (node (ref "IC11") (pin "6") (pinfunction "GND_6") (pintype "passive"))
      (node (ref "IC11") (pin "7") (pinfunction "GND_7") (pintype "passive"))
      (node (ref "IC11") (pin "9") (pinfunction "DGND_9") (pintype "passive"))
      (node (ref "IC11") (pin "PAD") (pinfunction "PAD_PAD") (pintype "passive"))
      (node (ref "IC12") (pin "1") (pinfunction "GND_1") (pintype "passive"))
      (node (ref "IC12") (pin "11") (pinfunction "LS_11") (pintype "input"))
      (node (ref "IC12") (pin "3") (pinfunction "GND_3") (pintype "passive"))
      (node (ref "IC12") (pin "4") (pinfunction "GND/NC_4") (pintype "passive"))
      (node (ref "IC12") (pin "6") (pinfunction "GND_6") (pintype "passive"))
      (node (ref "IC12") (pin "7") (pinfunction "GND_7") (pintype "passive"))
      (node (ref "IC12") (pin "9") (pinfunction "DGND_9") (pintype "passive"))
      (node (ref "IC12") (pin "PAD") (pinfunction "PAD_PAD") (pintype "passive"))
      (node (ref "IC5") (pin "AJ7") (pinfunction "rfsn_l_RFE_2_AJ7") (pintype "passive"))
      (node (ref "IC5") (pin "AJ9") (pinfunction "rfsp_l_RFE_2_AJ9") (pintype "passive"))
      (node (ref "IC5") (pin "AK12") (pinfunction "rfsn_l_RFE_1_AK12") (pintype "passive"))
      (node (ref "IC5") (pin "AL13") (pinfunction "rfsp_l_RFE_1_AL13") (pintype "passive"))
      (node (ref "IC5") (pin "AM12") (pinfunction "rfgn_l_RFE_1_AM12") (pintype "passive"))
      (node (ref "IC5") (pin "AN11") (pinfunction "rfgp_l_RFE_1_AN11") (pintype "passive"))
      (node (ref "IC5") (pin "AN5") (pinfunction "rfgp_l_RFE_2_AN5") (pintype "passive"))
      (node (ref "IC5") (pin "AP6") (pinfunction "rfgn_l_RFE_2_AP6") (pintype "passive"))
      (node (ref "J3") (pin "2") (pinfunction "Y_2") (pintype "passive"))
      (node (ref "J4") (pin "2") (pinfunction "Y_2") (pintype "passive"))
      (node (ref "J5") (pin "2") (pinfunction "Y_2") (pintype "passive"))
      (node (ref "J6") (pin "2") (pinfunction "Y_2") (pintype "passive"))
      (node (ref "J7") (pin "2") (pinfunction "Y_2") (pintype "passive"))
      (node (ref "T13") (pin "2") (pinfunction "2_2") (pintype "passive"))
      (node (ref "T14") (pin "2") (pinfunction "2_2") (pintype "passive"))
      (node (ref "T15") (pin "3") (pinfunction "3_3") (pintype "passive"))
      (node (ref "T16") (pin "2") (pinfunction "2_2") (pintype "passive"))
      (node (ref "T17") (pin "2") (pinfunction "2_2") (pintype "passive"))
      (node (ref "T18") (pin "1") (pinfunction "1_1") (pintype "passive"))
      (node (ref "T19") (pin "3") (pinfunction "3_3") (pintype "passive"))
    )
    (net (code "43") (name "Net-(C63-Pad2)") (class "Default")
      (node (ref "C63") (pin "2") (pinfunction "2_2") (pintype "passive"))
      (node (ref "T13") (pin "3") (pinfunction "3_3") (pintype "passive"))
    )
    (net (code "44") (name "Net-(C64-Pad2)") (class "Default")
      (node (ref "C64") (pin "2") (pinfunction "2_2") (pintype "passive"))
      (node (ref "T14") (pin "3") (pinfunction "3_3") (pintype "passive"))
    )
    (net (code "45") (name "Net-(C69-Pad2)") (class "Default")
      (node (ref "C69") (pin "2") (pinfunction "2_2") (pintype "passive"))
      (node (ref "T15") (pin "1") (pinfunction "1_1") (pintype "passive"))
    )
    (net (code "46") (name "Net-(C70-Pad2)") (class "Default")
      (node (ref "C70") (pin "2") (pinfunction "2_2") (pintype "passive"))
      (node (ref "T16") (pin "3") (pinfunction "3_3") (pintype "passive"))
    )
    (net (code "47") (name "Net-(C71-Pad2)") (class "Default")
      (node (ref "C71") (pin "2") (pinfunction "2_2") (pintype "passive"))
      (node (ref "T17") (pin "3") (pinfunction "3_3") (pintype "passive"))
    )
    (net (code "48") (name "Net-(C72-Pad2)") (class "Default")
      (node (ref "C72") (pin "2") (pinfunction "2_2") (pintype "passive"))
      (node (ref "T18") (pin "3") (pinfunction "3_3") (pintype "passive"))
    )
    (net (code "49") (name "Net-(C73-Pad2)") (class "Default")
      (node (ref "C73") (pin "2") (pinfunction "2_2") (pintype "passive"))
      (node (ref "T19") (pin "1") (pinfunction "1_1") (pintype "passive"))
    )
    (net (code "50") (name "Net-(IC5D-rfgn_h_RFE_2)") (class "Default")
      (node (ref "IC5") (pin "AM8") (pinfunction "rfgn_h_RFE_2_AM8") (pintype "passive"))
      (node (ref "MN101") (pin "1") (pinfunction "1_1") (pintype "passive"))
      (node (ref "MN104") (pin "2") (pinfunction "2_2") (pintype "passive"))
    )
    (net (code "51") (name "Net-(IC11-RF1)") (class "Default")
      (node (ref "C76") (pin "1") (pinfunction "1_1") (pintype "passive"))
      (node (ref "IC11") (pin "8") (pinfunction "RF1_8") (pintype "bidirectional"))
    )
    (net (code "52") (name "Net-(IC11-RF2)") (class "Default")
      (node (ref "C74") (pin "1") (pinfunction "1_1") (pintype "passive"))
      (node (ref "IC11") (pin "2") (pinfunction "RF2_2") (pintype "bidirectional"))
    )
    (net (code "53") (name "Net-(IC12-RF1)") (class "Default")
      (node (ref "C77") (pin "1") (pinfunction "1_1") (pintype "passive"))
      (node (ref "IC12") (pin "8") (pinfunction "RF1_8") (pintype "bidirectional"))
    )
    (net (code "54") (name "Net-(IC12-RF2)") (class "Default")
      (node (ref "C75") (pin "1") (pinfunction "1_1") (pintype "passive"))
      (node (ref "IC12") (pin "2") (pinfunction "RF2_2") (pintype "bidirectional"))
    )
    (net (code "55") (name "Net-(MN73-Pad1)") (class "Default")
      (node (ref "MN73") (pin "1") (pinfunction "1_1") (pintype "passive"))
      (node (ref "MN77") (pin "2") (pinfunction "2_2") (pintype "passive"))
    )
    (net (code "56") (name "Net-(MN74-Pad1)") (class "Default")
      (node (ref "MN74") (pin "1") (pinfunction "1_1") (pintype "passive"))
      (node (ref "MN78") (pin "2") (pinfunction "2_2") (pintype "passive"))
    )
    (net (code "57") (name "Net-(MN75-Pad1)") (class "Default")
      (node (ref "MN75") (pin "1") (pinfunction "1_1") (pintype "passive"))
      (node (ref "MN79") (pin "2") (pinfunction "2_2") (pintype "passive"))
    )
    (net (code "58") (name "Net-(MN76-Pad1)") (class "Default")
      (node (ref "MN76") (pin "1") (pinfunction "1_1") (pintype "passive"))
      (node (ref "MN80") (pin "2") (pinfunction "2_2") (pintype "passive"))
    )
    (net (code "59") (name "Net-(MN89-Pad1)") (class "Default")
      (node (ref "MN89") (pin "1") (pinfunction "1_1") (pintype "passive"))
      (node (ref "MN91") (pin "2") (pinfunction "2_2") (pintype "passive"))
    )
    (net (code "60") (name "Net-(MN90-Pad1)") (class "Default")
      (node (ref "MN90") (pin "1") (pinfunction "1_1") (pintype "passive"))
      (node (ref "MN92") (pin "2") (pinfunction "2_2") (pintype "passive"))
    )
    (net (code "61") (name "VCC1P8_LMS3") (class "Default")
      (node (ref "C55") (pin "2") (pinfunction "2_2") (pintype "passive"))
      (node (ref "C56") (pin "2") (pinfunction "2_2") (pintype "passive"))
      (node (ref "C57") (pin "2") (pinfunction "2_2") (pintype "passive"))
      (node (ref "C58") (pin "2") (pinfunction "2_2") (pintype "passive"))
      (node (ref "C59") (pin "2") (pinfunction "2_2") (pintype "passive"))
      (node (ref "C60") (pin "2") (pinfunction "2_2") (pintype "passive"))
      (node (ref "C61") (pin "2") (pinfunction "2_2") (pintype "passive"))
      (node (ref "C62") (pin "2") (pinfunction "2_2") (pintype "passive"))
      (node (ref "C65") (pin "2") (pinfunction "2_2") (pintype "passive"))
      (node (ref "C66") (pin "2") (pinfunction "2_2") (pintype "passive"))
      (node (ref "C67") (pin "2") (pinfunction "2_2") (pintype "passive"))
      (node (ref "C68") (pin "2") (pinfunction "2_2") (pintype "passive"))
      (node (ref "MN73") (pin "2") (pinfunction "2_2") (pintype "passive"))
      (node (ref "MN74") (pin "2") (pinfunction "2_2") (pintype "passive"))
      (node (ref "MN75") (pin "2") (pinfunction "2_2") (pintype "passive"))
      (node (ref "MN76") (pin "2") (pinfunction "2_2") (pintype "passive"))
      (node (ref "MN89") (pin "2") (pinfunction "2_2") (pintype "passive"))
      (node (ref "MN90") (pin "2") (pinfunction "2_2") (pintype "passive"))
    )
    (net (code "62") (name "VCC3P3_RF") (class "Default")
      (node (ref "C80") (pin "2") (pinfunction "2_2") (pintype "passive"))
      (node (ref "C81") (pin "2") (pinfunction "2_2") (pintype "passive"))
      (node (ref "IC11") (pin "12") (pinfunction "VDD_12") (pintype "power_in"))
      (node (ref "IC12") (pin "12") (pinfunction "VDD_12") (pintype "power_in"))
    )
    (net (code "63") (name "unconnected-(IC5C-pa2on_1-PadB10)") (class "Default")
      (node (ref "IC5") (pin "B10") (pinfunction "pa2on_1_B10") (pintype "passive+no_connect"))
    )
    (net (code "64") (name "unconnected-(IC5C-pa2op_1-PadA9)") (class "Default")
      (node (ref "IC5") (pin "A9") (pinfunction "pa2op_1_A9") (pintype "passive+no_connect"))
    )
    (net (code "65") (name "unconnected-(T15-Pad2)") (class "Default")
      (node (ref "T15") (pin "2") (pinfunction "2_2") (pintype "passive+no_connect"))
    )
    (net (code "66") (name "unconnected-(T18-Pad2)") (class "Default")
      (node (ref "T18") (pin "2") (pinfunction "2_2") (pintype "passive+no_connect"))
    )
    (net (code "67") (name "unconnected-(T19-Pad2)") (class "Default")
      (node (ref "T19") (pin "2") (pinfunction "2_2") (pintype "passive+no_connect"))
    )
  )
)
